# STLink_V3E_PWR.net
KiCad netlist of a schematic drawn in Altium Designer
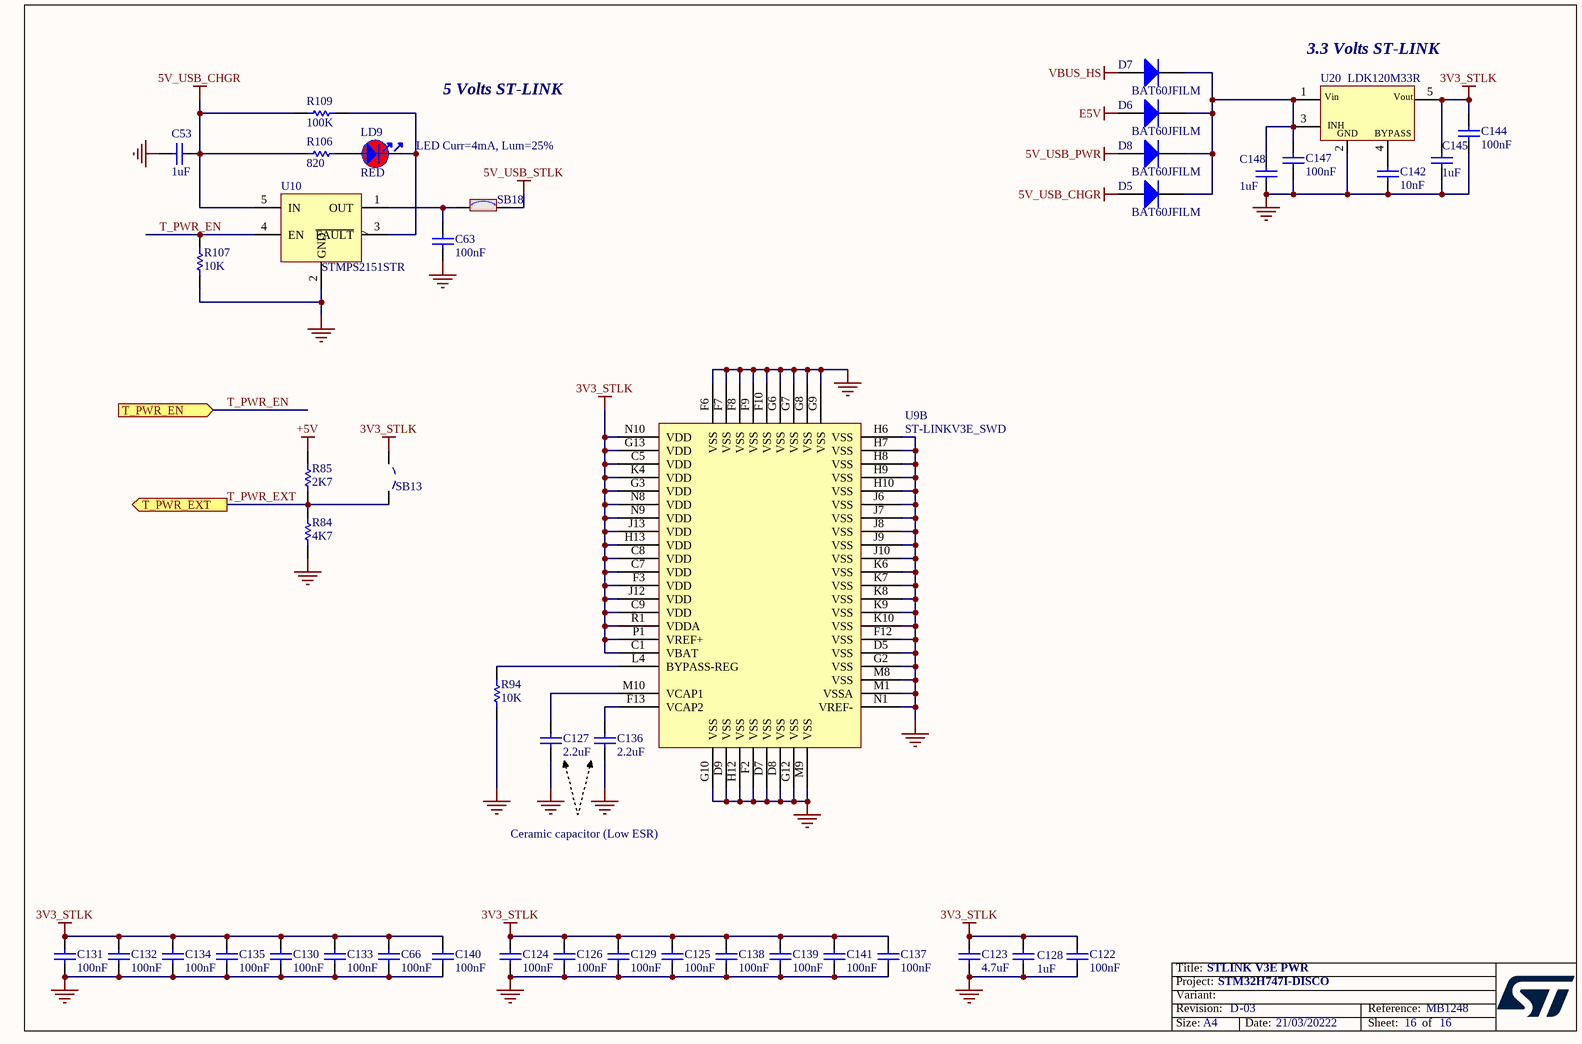
[diagram p0: STLink_V3E_PWR.SchDoc]

(export (version "E")
  (design (tool "Eeschema 10.0.6"))
  (components
    (comp (ref "C53")
      (value "1uF")
      (footprint "0603C")
      (description "Capacitor,1uF,16V,X5R,10%,0603")
      (fields
        (field (name "INTERNAL_PART_NUMBER") "MCD-00010")
        (field (name "MANUFACTURER_PART_NUMBER") "CC0603KRX5R7BB105")
        (field (name "PROVIDED_BY") "Subcon")
      )
      (libsource (lib "MCD_PARTS_database") (part "Capacitor"))
    )
    (comp (ref "C63")
      (value "100nF")
      (footprint "0603C")
      (description "Capacitor, MLCC, 100nF, 16V, X7R, 10%, 0402, T=0.5mm")
      (fields
        (field (name "INTERNAL_PART_NUMBER") "MCD-00006")
        (field (name "MANUFACTURER_PART_NUMBER") "CC0402KRX7R7BB104")
        (field (name "PROVIDED_BY") "Subcon")
      )
      (libsource (lib "MCD_PARTS_database") (part "Capacitor"))
    )
    (comp (ref "C66")
      (value "100nF")
      (footprint "0402C")
      (description "Capacitor,100nF,16V,X7R,10%,0402")
      (fields
        (field (name "INTERNAL_PART_NUMBER") "MCD-00102")
        (field (name "MANUFACTURER_PART_NUMBER") "CC0402KRX7R7BB104")
        (field (name "PROVIDED_BY") "Subcon")
      )
      (libsource (lib "MCD_PARTS_database") (part "Capacitor"))
    )
    (comp (ref "C122")
      (value "100nF")
      (footprint "0603C")
      (description "Capacitor,100nF,16V,X7R,10%,0603")
      (fields
        (field (name "INTERNAL_PART_NUMBER") "MCD-00211")
        (field (name "MANUFACTURER_PART_NUMBER") "CC0603KRX7R7BB104")
        (field (name "PROVIDED_BY") "Subcon")
      )
      (libsource (lib "MCD_PARTS_database") (part "Capacitor"))
    )
    (comp (ref "C123")
      (value "4.7uF")
      (footprint "0603C")
      (description "Capacitor,4.7uF,16V, X5R,10%,0603")
      (fields
        (field (name "INTERNAL_PART_NUMBER") "MCD-00009")
        (field (name "MANUFACTURER_PART_NUMBER") "CC0603KRX5R7BB475")
        (field (name "PROVIDED_BY") "subcon")
      )
      (libsource (lib "MCD_PARTS_database") (part "Capacitor"))
    )
    (comp (ref "C124")
      (value "100nF")
      (footprint "0402C")
      (description "Capacitor,100nF,16V,X7R,10%,0402")
      (fields
        (field (name "INTERNAL_PART_NUMBER") "MCD-00102")
        (field (name "MANUFACTURER_PART_NUMBER") "CC0402KRX7R7BB104")
        (field (name "PROVIDED_BY") "Subcon")
      )
      (libsource (lib "MCD_PARTS_database") (part "Capacitor"))
    )
    (comp (ref "C125")
      (value "100nF")
      (footprint "0402C")
      (description "Capacitor,100nF,16V,X7R,10%,0402")
      (fields
        (field (name "INTERNAL_PART_NUMBER") "MCD-00102")
        (field (name "MANUFACTURER_PART_NUMBER") "CC0402KRX7R7BB104")
        (field (name "PROVIDED_BY") "Subcon")
      )
      (libsource (lib "MCD_PARTS_database") (part "Capacitor"))
    )
    (comp (ref "C126")
      (value "100nF")
      (footprint "0402C")
      (description "Capacitor,100nF,16V,X7R,10%,0402")
      (fields
        (field (name "INTERNAL_PART_NUMBER") "MCD-00102")
        (field (name "MANUFACTURER_PART_NUMBER") "CC0402KRX7R7BB104")
        (field (name "PROVIDED_BY") "Subcon")
      )
      (libsource (lib "MCD_PARTS_database") (part "Capacitor"))
    )
    (comp (ref "C127")
      (value "2.2uF")
      (footprint "1206C")
      (description "Capacitor,2.2uF,16V, X7R,10%,1206")
      (fields
        (field (name "INTERNAL_PART_NUMBER") "MCD-00008")
        (field (name "MANUFACTURER_PART_NUMBER") "CC1206KKX7R7BB225")
        (field (name "PROVIDED_BY") "Subcon")
      )
      (libsource (lib "MCD_PARTS_database") (part "Capacitor"))
    )
    (comp (ref "C128")
      (value "1uF")
      (footprint "0603C")
      (description "Capacitor,1uF,16V,X5R,10%,0603")
      (fields
        (field (name "INTERNAL_PART_NUMBER") "MCD-00010")
        (field (name "MANUFACTURER_PART_NUMBER") "CC0603KRX5R7BB105")
        (field (name "PROVIDED_BY") "Subcon")
      )
      (libsource (lib "MCD_PARTS_database") (part "Capacitor"))
    )
    (comp (ref "C129")
      (value "100nF")
      (footprint "0402C")
      (description "Capacitor,100nF,16V,X7R,10%,0402")
      (fields
        (field (name "INTERNAL_PART_NUMBER") "MCD-00102")
        (field (name "MANUFACTURER_PART_NUMBER") "CC0402KRX7R7BB104")
        (field (name "PROVIDED_BY") "Subcon")
      )
      (libsource (lib "MCD_PARTS_database") (part "Capacitor"))
    )
    (comp (ref "C130")
      (value "100nF")
      (footprint "0402C")
      (description "Capacitor,100nF,16V,X7R,10%,0402")
      (fields
        (field (name "INTERNAL_PART_NUMBER") "MCD-00102")
        (field (name "MANUFACTURER_PART_NUMBER") "CC0402KRX7R7BB104")
        (field (name "PROVIDED_BY") "Subcon")
      )
      (libsource (lib "MCD_PARTS_database") (part "Capacitor"))
    )
    (comp (ref "C131")
      (value "100nF")
      (footprint "0402C")
      (description "Capacitor,100nF,16V,X7R,10%,0402")
      (fields
        (field (name "INTERNAL_PART_NUMBER") "MCD-00102")
        (field (name "MANUFACTURER_PART_NUMBER") "CC0402KRX7R7BB104")
        (field (name "PROVIDED_BY") "Subcon")
      )
      (libsource (lib "MCD_PARTS_database") (part "Capacitor"))
    )
    (comp (ref "C132")
      (value "100nF")
      (footprint "0402C")
      (description "Capacitor,100nF,16V,X7R,10%,0402")
      (fields
        (field (name "INTERNAL_PART_NUMBER") "MCD-00102")
        (field (name "MANUFACTURER_PART_NUMBER") "CC0402KRX7R7BB104")
        (field (name "PROVIDED_BY") "Subcon")
      )
      (libsource (lib "MCD_PARTS_database") (part "Capacitor"))
    )
    (comp (ref "C133")
      (value "100nF")
      (footprint "0402C")
      (description "Capacitor,100nF,16V,X7R,10%,0402")
      (fields
        (field (name "INTERNAL_PART_NUMBER") "MCD-00102")
        (field (name "MANUFACTURER_PART_NUMBER") "CC0402KRX7R7BB104")
        (field (name "PROVIDED_BY") "Subcon")
      )
      (libsource (lib "MCD_PARTS_database") (part "Capacitor"))
    )
    (comp (ref "C134")
      (value "100nF")
      (footprint "0402C")
      (description "Capacitor,100nF,16V,X7R,10%,0402")
      (fields
        (field (name "INTERNAL_PART_NUMBER") "MCD-00102")
        (field (name "MANUFACTURER_PART_NUMBER") "CC0402KRX7R7BB104")
        (field (name "PROVIDED_BY") "Subcon")
      )
      (libsource (lib "MCD_PARTS_database") (part "Capacitor"))
    )
    (comp (ref "C135")
      (value "100nF")
      (footprint "0402C")
      (description "Capacitor,100nF,16V,X7R,10%,0402")
      (fields
        (field (name "INTERNAL_PART_NUMBER") "MCD-00102")
        (field (name "MANUFACTURER_PART_NUMBER") "CC0402KRX7R7BB104")
        (field (name "PROVIDED_BY") "Subcon")
      )
      (libsource (lib "MCD_PARTS_database") (part "Capacitor"))
    )
    (comp (ref "C136")
      (value "2.2uF")
      (footprint "1206C")
      (description "Capacitor,2.2uF,16V, X7R,10%,1206")
      (fields
        (field (name "INTERNAL_PART_NUMBER") "MCD-00008")
        (field (name "MANUFACTURER_PART_NUMBER") "CC1206KKX7R7BB225")
        (field (name "PROVIDED_BY") "Subcon")
      )
      (libsource (lib "MCD_PARTS_database") (part "Capacitor"))
    )
    (comp (ref "C137")
      (value "100nF")
      (footprint "0402C")
      (description "Capacitor,100nF,16V,X7R,10%,0402")
      (fields
        (field (name "INTERNAL_PART_NUMBER") "MCD-00102")
        (field (name "MANUFACTURER_PART_NUMBER") "CC0402KRX7R7BB104")
        (field (name "PROVIDED_BY") "Subcon")
      )
      (libsource (lib "MCD_PARTS_database") (part "Capacitor"))
    )
    (comp (ref "C138")
      (value "100nF")
      (footprint "0402C")
      (description "Capacitor,100nF,16V,X7R,10%,0402")
      (fields
        (field (name "INTERNAL_PART_NUMBER") "MCD-00102")
        (field (name "MANUFACTURER_PART_NUMBER") "CC0402KRX7R7BB104")
        (field (name "PROVIDED_BY") "Subcon")
      )
      (libsource (lib "MCD_PARTS_database") (part "Capacitor"))
    )
    (comp (ref "C139")
      (value "100nF")
      (footprint "0402C")
      (description "Capacitor,100nF,16V,X7R,10%,0402")
      (fields
        (field (name "INTERNAL_PART_NUMBER") "MCD-00102")
        (field (name "MANUFACTURER_PART_NUMBER") "CC0402KRX7R7BB104")
        (field (name "PROVIDED_BY") "Subcon")
      )
      (libsource (lib "MCD_PARTS_database") (part "Capacitor"))
    )
    (comp (ref "C140")
      (value "100nF")
      (footprint "0402C")
      (description "Capacitor,100nF,16V,X7R,10%,0402")
      (fields
        (field (name "INTERNAL_PART_NUMBER") "MCD-00102")
        (field (name "MANUFACTURER_PART_NUMBER") "CC0402KRX7R7BB104")
        (field (name "PROVIDED_BY") "Subcon")
      )
      (libsource (lib "MCD_PARTS_database") (part "Capacitor"))
    )
    (comp (ref "C141")
      (value "100nF")
      (footprint "0402C")
      (description "Capacitor,100nF,16V,X7R,10%,0402")
      (fields
        (field (name "INTERNAL_PART_NUMBER") "MCD-00102")
        (field (name "MANUFACTURER_PART_NUMBER") "CC0402KRX7R7BB104")
        (field (name "PROVIDED_BY") "Subcon")
      )
      (libsource (lib "MCD_PARTS_database") (part "Capacitor"))
    )
    (comp (ref "C142")
      (value "10nF")
      (footprint "0603C")
      (description "Capacitor,10nF,50V,X7R,10%,0603")
      (fields
        (field (name "INTERNAL_PART_NUMBER") "MCD-00017")
        (field (name "MANUFACTURER_PART_NUMBER") "CC0603KRX7R9BB103")
        (field (name "PROVIDED_BY") "Subcon")
      )
      (libsource (lib "MCD_PARTS_database") (part "Capacitor"))
    )
    (comp (ref "C144")
      (value "100nF")
      (footprint "0603C")
      (description "Capacitor,100nF,16V,X7R,10%,0603")
      (fields
        (field (name "INTERNAL_PART_NUMBER") "MCD-00211")
        (field (name "MANUFACTURER_PART_NUMBER") "CC0603KRX7R7BB104")
        (field (name "PROVIDED_BY") "Subcon")
      )
      (libsource (lib "MCD_PARTS_database") (part "Capacitor"))
    )
    (comp (ref "C145")
      (value "1uF")
      (footprint "0603C")
      (description "Capacitor,1uF,16V,X5R,10%,0603")
      (fields
        (field (name "INTERNAL_PART_NUMBER") "MCD-00010")
        (field (name "MANUFACTURER_PART_NUMBER") "CC0603KRX5R7BB105")
        (field (name "PROVIDED_BY") "Subcon")
      )
      (libsource (lib "MCD_PARTS_database") (part "Capacitor"))
    )
    (comp (ref "C147")
      (value "100nF")
      (footprint "0603C")
      (description "Capacitor,100nF,16V,X7R,10%,0603")
      (fields
        (field (name "INTERNAL_PART_NUMBER") "MCD-00211")
        (field (name "MANUFACTURER_PART_NUMBER") "CC0603KRX7R7BB104")
        (field (name "PROVIDED_BY") "Subcon")
      )
      (libsource (lib "MCD_PARTS_database") (part "Capacitor"))
    )
    (comp (ref "C148")
      (value "1uF")
      (footprint "0603C")
      (description "Capacitor,1uF,6V3,X5R,10%,0603")
      (fields
        (field (name "INTERNAL_PART_NUMBER") "MCD-00238")
        (field (name "MANUFACTURER_PART_NUMBER") "CC0603KRX5R5BB105")
        (field (name "PROVIDED_BY") "Subcon")
      )
      (libsource (lib "MCD_PARTS_database") (part "Capacitor"))
    )
    (comp (ref "D5")
      (value "BAT60JFILM")
      (footprint "SOD-323")
      (fields (field (name "INTERNAL_PART_NUMBER") "MCD-00034"))
      (libsource (lib "MCD_PARTS_database") (part "BAT60JFILM"))
    )
    (comp (ref "D6")
      (value "BAT60JFILM")
      (footprint "SOD-323")
      (fields (field (name "INTERNAL_PART_NUMBER") "MCD-00034"))
      (libsource (lib "MCD_PARTS_database") (part "BAT60JFILM"))
    )
    (comp (ref "D7")
      (value "BAT60JFILM")
      (footprint "SOD-323")
      (fields (field (name "INTERNAL_PART_NUMBER") "MCD-00034"))
      (libsource (lib "MCD_PARTS_database") (part "BAT60JFILM"))
    )
    (comp (ref "D8")
      (value "BAT60JFILM")
      (footprint "SOD-323")
      (fields (field (name "INTERNAL_PART_NUMBER") "MCD-00034"))
      (libsource (lib "MCD_PARTS_database") (part "BAT60JFILM"))
    )
    (comp (ref "LD9")
      (value "RED")
      (footprint "0603D")
      (description "LED Red, 0603 SMD, 2V Forward Voltage")
      (fields
        (field (name "INTERNAL_PART_NUMBER") "MCD-00587")
        (field (name "MANUFACTURER_PART_NUMBER") "VLMS1300-GS08")
        (field (name "PROVIDED_BY") "Subcon")
      )
      (libsource (lib "MCD_PARTS_database") (part "LED_red"))
    )
    (comp (ref "R84")
      (value "4K7")
      (footprint "0402R")
      (description "Resistor,4K7,0402,1%,1/16W")
      (fields
        (field (name "INTERNAL_PART_NUMBER") "MCD-00065")
        (field (name "MANUFACTURER_PART_NUMBER") "RC0402FR-074K7L")
        (field (name "PROVIDED_BY") "Subcon")
      )
      (libsource (lib "MCD_PARTS_database") (part "Resistor"))
    )
    (comp (ref "R85")
      (value "2K7")
      (footprint "0402R")
      (description "Resistor,2K7,0402,1%,1/16W")
      (fields
        (field (name "INTERNAL_PART_NUMBER") "MCD-00055")
        (field (name "MANUFACTURER_PART_NUMBER") "RC0402FR-072K7L")
        (field (name "PROVIDED_BY") "Subcon")
      )
      (libsource (lib "MCD_PARTS_database") (part "Resistor"))
    )
    (comp (ref "R94")
      (value "10K")
      (footprint "0402R")
      (description "Resistor,10K,0402,1%,1/16W")
      (fields
        (field (name "INTERNAL_PART_NUMBER") "MCD-00053")
        (field (name "MANUFACTURER_PART_NUMBER") "RC0402FR-0710KL")
        (field (name "PROVIDED_BY") "subcon")
      )
      (libsource (lib "MCD_PARTS_database") (part "Resistor"))
    )
    (comp (ref "R106")
      (value "820")
      (footprint "0603R")
      (description "Resistor,820R,0402,1%,1/16W")
      (fields
        (field (name "INTERNAL_PART_NUMBER") "MCD-00527")
        (field (name "MANUFACTURER_PART_NUMBER") "RC0402FR-07820RL")
        (field (name "PROVIDED_BY") "Subcon")
      )
      (libsource (lib "MCD_PARTS_database") (part "Resistor"))
    )
    (comp (ref "R107")
      (value "10K")
      (footprint "0603R")
      (description "Resistor,10K,0402,1%,1/16W")
      (fields
        (field (name "INTERNAL_PART_NUMBER") "MCD-00053")
        (field (name "MANUFACTURER_PART_NUMBER") "RC0402FR-0710KL")
        (field (name "PROVIDED_BY") "subcon")
      )
      (libsource (lib "MCD_PARTS_database") (part "Resistor"))
    )
    (comp (ref "R109")
      (value "100K")
      (footprint "0402R")
      (description "Resistor,100K,0402,1%,1/16W")
      (fields
        (field (name "INTERNAL_PART_NUMBER") "MCD-00059")
        (field (name "MANUFACTURER_PART_NUMBER") "RC0402FR-07100KL")
        (field (name "PROVIDED_BY") "Subcon")
      )
      (libsource (lib "MCD_PARTS_database") (part "Resistor"))
    )
    (comp (ref "SB13")
      (value "Solder Bridge OFF")
      (footprint "SB_0603")
      (libsource (lib "MCD_TOOLS") (part "SB_OFF"))
    )
    (comp (ref "SB18")
      (value "Solder Bridge ON")
      (footprint "SB_0603")
      (libsource (lib "MCD_TOOLS") (part "SB_ON"))
    )
    (comp (ref "U9")
      (value "ST-LINKV3E_SWD")
      (footprint "BGA176_0R65_10x10")
      (description "STM32F723IEK  (STM32F7 LittleBirdie) BGA176")
      (fields (field (name "INTERNAL_PART_NUMBER") "MCD-00596"))
      (libsource (lib "MB1248_1") (part "ST-LINKV3E_SWD"))
    )
    (comp (ref "U10")
      (value "STMPS2151STR")
      (footprint "SOT23-5")
      (description "500mA, Enhanced single channel power switches with active high enable pin")
      (fields
        (field (name "INTERNAL_PART_NUMBER") "MCD-00159")
        (field (name "MANUFACTURER") "STMICROELECTRONICS")
        (field (name "PROVIDED_BY") "Subcon")
      )
      (libsource (lib "MCD_PARTS_database") (part "STMPS2151STR"))
    )
    (comp (ref "U20")
      (value "LDK120M33R")
      (footprint "SOT23-5")
      (description "Ultra low drop-low noise BiCMOS voltage, regulators low ESR capacitors compatible")
      (fields (field (name "INTERNAL_PART_NUMBER") "MCD-00086"))
      (libsource (lib "MCD_PARTS_database") (part "LD3985M33R"))
    )
  )
  (nets
    (net (code "1") (name "+5V") (class "Default")
      (node (ref "R85") (pin "2") (pinfunction "2_2") (pintype "passive"))
    )
    (net (code "2") (name "/T_PWR_EN") (class "Default")
      (node (ref "R107") (pin "2") (pinfunction "2_2") (pintype "passive"))
      (node (ref "U10") (pin "4") (pinfunction "EN_4") (pintype "passive"))
    )
    (net (code "3") (name "/T_PWR_EXT") (class "Default")
      (node (ref "R84") (pin "2") (pinfunction "2_2") (pintype "passive"))
      (node (ref "R85") (pin "1") (pinfunction "1_1") (pintype "passive"))
      (node (ref "SB13") (pin "2") (pinfunction "2_2") (pintype "passive"))
    )
    (net (code "4") (name "3V3_STLK") (class "Default")
      (node (ref "C122") (pin "2") (pinfunction "2_2") (pintype "passive"))
      (node (ref "C123") (pin "2") (pinfunction "2_2") (pintype "passive"))
      (node (ref "C124") (pin "2") (pinfunction "2_2") (pintype "passive"))
      (node (ref "C125") (pin "2") (pinfunction "2_2") (pintype "passive"))
      (node (ref "C126") (pin "2") (pinfunction "2_2") (pintype "passive"))
      (node (ref "C128") (pin "2") (pinfunction "2_2") (pintype "passive"))
      (node (ref "C129") (pin "2") (pinfunction "2_2") (pintype "passive"))
      (node (ref "C130") (pin "2") (pinfunction "2_2") (pintype "passive"))
      (node (ref "C131") (pin "2") (pinfunction "2_2") (pintype "passive"))
      (node (ref "C132") (pin "2") (pinfunction "2_2") (pintype "passive"))
      (node (ref "C133") (pin "2") (pinfunction "2_2") (pintype "passive"))
      (node (ref "C134") (pin "2") (pinfunction "2_2") (pintype "passive"))
      (node (ref "C135") (pin "2") (pinfunction "2_2") (pintype "passive"))
      (node (ref "C137") (pin "2") (pinfunction "2_2") (pintype "passive"))
      (node (ref "C138") (pin "2") (pinfunction "2_2") (pintype "passive"))
      (node (ref "C139") (pin "2") (pinfunction "2_2") (pintype "passive"))
      (node (ref "C140") (pin "2") (pinfunction "2_2") (pintype "passive"))
      (node (ref "C141") (pin "2") (pinfunction "2_2") (pintype "passive"))
      (node (ref "C144") (pin "2") (pinfunction "2_2") (pintype "passive"))
      (node (ref "C145") (pin "2") (pinfunction "2_2") (pintype "passive"))
      (node (ref "C66") (pin "2") (pinfunction "2_2") (pintype "passive"))
      (node (ref "SB13") (pin "1") (pinfunction "1_1") (pintype "passive"))
      (node (ref "U20") (pin "5") (pinfunction "Vout_5") (pintype "passive"))
      (node (ref "U9") (pin "C1") (pinfunction "VBAT_C1") (pintype "passive"))
      (node (ref "U9") (pin "C5") (pinfunction "VDD_C5") (pintype "passive"))
      (node (ref "U9") (pin "C7") (pinfunction "VDD_C7") (pintype "passive"))
      (node (ref "U9") (pin "C8") (pinfunction "VDD_C8") (pintype "passive"))
      (node (ref "U9") (pin "C9") (pinfunction "VDD_C9") (pintype "passive"))
      (node (ref "U9") (pin "F3") (pinfunction "VDD_F3") (pintype "passive"))
      (node (ref "U9") (pin "G13") (pinfunction "VDD_G13") (pintype "passive"))
      (node (ref "U9") (pin "G3") (pinfunction "VDD_G3") (pintype "passive"))
      (node (ref "U9") (pin "H13") (pinfunction "VDD_H13") (pintype "passive"))
      (node (ref "U9") (pin "J12") (pinfunction "VDD_J12") (pintype "passive"))
      (node (ref "U9") (pin "J13") (pinfunction "VDD_J13") (pintype "passive"))
      (node (ref "U9") (pin "K4") (pinfunction "VDD_K4") (pintype "passive"))
      (node (ref "U9") (pin "N10") (pinfunction "VDD_N10") (pintype "passive"))
      (node (ref "U9") (pin "N8") (pinfunction "VDD_N8") (pintype "passive"))
      (node (ref "U9") (pin "N9") (pinfunction "VDD_N9") (pintype "passive"))
      (node (ref "U9") (pin "P1") (pinfunction "VREF+_P1") (pintype "passive"))
      (node (ref "U9") (pin "R1") (pinfunction "VDDA_R1") (pintype "passive"))
    )
    (net (code "5") (name "5V_USB_CHGR") (class "Default")
      (node (ref "C53") (pin "1") (pinfunction "1_1") (pintype "passive"))
      (node (ref "D5") (pin "1") (pinfunction "A_1") (pintype "passive"))
      (node (ref "R106") (pin "1") (pinfunction "1_1") (pintype "passive"))
      (node (ref "R109") (pin "2") (pinfunction "2_2") (pintype "passive"))
      (node (ref "U10") (pin "5") (pinfunction "IN_5") (pintype "passive"))
    )
    (net (code "6") (name "5V_USB_PWR") (class "Default")
      (node (ref "D8") (pin "1") (pinfunction "A_1") (pintype "passive"))
    )
    (net (code "7") (name "5V_USB_STLK") (class "Default")
      (node (ref "SB18") (pin "2") (pinfunction "2_2") (pintype "passive"))
    )
    (net (code "8") (name "E5V") (class "Default")
      (node (ref "D6") (pin "1") (pinfunction "A_1") (pintype "passive"))
    )
    (net (code "9") (name "GND") (class "Default")
      (node (ref "C122") (pin "1") (pinfunction "1_1") (pintype "passive"))
      (node (ref "C123") (pin "1") (pinfunction "1_1") (pintype "passive"))
      (node (ref "C124") (pin "1") (pinfunction "1_1") (pintype "passive"))
      (node (ref "C125") (pin "1") (pinfunction "1_1") (pintype "passive"))
      (node (ref "C126") (pin "1") (pinfunction "1_1") (pintype "passive"))
      (node (ref "C127") (pin "1") (pinfunction "1_1") (pintype "passive"))
      (node (ref "C128") (pin "1") (pinfunction "1_1") (pintype "passive"))
      (node (ref "C129") (pin "1") (pinfunction "1_1") (pintype "passive"))
      (node (ref "C130") (pin "1") (pinfunction "1_1") (pintype "passive"))
      (node (ref "C131") (pin "1") (pinfunction "1_1") (pintype "passive"))
      (node (ref "C132") (pin "1") (pinfunction "1_1") (pintype "passive"))
      (node (ref "C133") (pin "1") (pinfunction "1_1") (pintype "passive"))
      (node (ref "C134") (pin "1") (pinfunction "1_1") (pintype "passive"))
      (node (ref "C135") (pin "1") (pinfunction "1_1") (pintype "passive"))
      (node (ref "C136") (pin "1") (pinfunction "1_1") (pintype "passive"))
      (node (ref "C137") (pin "1") (pinfunction "1_1") (pintype "passive"))
      (node (ref "C138") (pin "1") (pinfunction "1_1") (pintype "passive"))
      (node (ref "C139") (pin "1") (pinfunction "1_1") (pintype "passive"))
      (node (ref "C140") (pin "1") (pinfunction "1_1") (pintype "passive"))
      (node (ref "C141") (pin "1") (pinfunction "1_1") (pintype "passive"))
      (node (ref "C142") (pin "1") (pinfunction "1_1") (pintype "passive"))
      (node (ref "C144") (pin "1") (pinfunction "1_1") (pintype "passive"))
      (node (ref "C145") (pin "1") (pinfunction "1_1") (pintype "passive"))
      (node (ref "C147") (pin "1") (pinfunction "1_1") (pintype "passive"))
      (node (ref "C148") (pin "2") (pinfunction "2_2") (pintype "passive"))
      (node (ref "C53") (pin "2") (pinfunction "2_2") (pintype "passive"))
      (node (ref "C63") (pin "1") (pinfunction "1_1") (pintype "passive"))
      (node (ref "C66") (pin "1") (pinfunction "1_1") (pintype "passive"))
      (node (ref "R107") (pin "1") (pinfunction "1_1") (pintype "passive"))
      (node (ref "R84") (pin "1") (pinfunction "1_1") (pintype "passive"))
      (node (ref "R94") (pin "1") (pinfunction "1_1") (pintype "passive"))
      (node (ref "U10") (pin "2") (pinfunction "GND_2") (pintype "passive"))
      (node (ref "U20") (pin "2") (pinfunction "GND_2") (pintype "passive"))
      (node (ref "U9") (pin "D5") (pinfunction "VSS_D5") (pintype "passive"))
      (node (ref "U9") (pin "D7") (pinfunction "VSS_D7") (pintype "passive"))
      (node (ref "U9") (pin "D8") (pinfunction "VSS_D8") (pintype "passive"))
      (node (ref "U9") (pin "D9") (pinfunction "VSS_D9") (pintype "passive"))
      (node (ref "U9") (pin "F10") (pinfunction "VSS_F10") (pintype "passive"))
      (node (ref "U9") (pin "F12") (pinfunction "VSS_F12") (pintype "passive"))
      (node (ref "U9") (pin "F2") (pinfunction "VSS_F2") (pintype "passive"))
      (node (ref "U9") (pin "F6") (pinfunction "VSS_F6") (pintype "passive"))
      (node (ref "U9") (pin "F7") (pinfunction "VSS_F7") (pintype "passive"))
      (node (ref "U9") (pin "F8") (pinfunction "VSS_F8") (pintype "passive"))
      (node (ref "U9") (pin "F9") (pinfunction "VSS_F9") (pintype "passive"))
      (node (ref "U9") (pin "G10") (pinfunction "VSS_G10") (pintype "passive"))
      (node (ref "U9") (pin "G12") (pinfunction "VSS_G12") (pintype "passive"))
      (node (ref "U9") (pin "G2") (pinfunction "VSS_G2") (pintype "passive"))
      (node (ref "U9") (pin "G6") (pinfunction "VSS_G6") (pintype "passive"))
      (node (ref "U9") (pin "G7") (pinfunction "VSS_G7") (pintype "passive"))
      (node (ref "U9") (pin "G8") (pinfunction "VSS_G8") (pintype "passive"))
      (node (ref "U9") (pin "G9") (pinfunction "VSS_G9") (pintype "passive"))
      (node (ref "U9") (pin "H10") (pinfunction "VSS_H10") (pintype "passive"))
      (node (ref "U9") (pin "H12") (pinfunction "VSS_H12") (pintype "passive"))
      (node (ref "U9") (pin "H6") (pinfunction "VSS_H6") (pintype "passive"))
      (node (ref "U9") (pin "H7") (pinfunction "VSS_H7") (pintype "passive"))
      (node (ref "U9") (pin "H8") (pinfunction "VSS_H8") (pintype "passive"))
      (node (ref "U9") (pin "H9") (pinfunction "VSS_H9") (pintype "passive"))
      (node (ref "U9") (pin "J10") (pinfunction "VSS_J10") (pintype "passive"))
      (node (ref "U9") (pin "J6") (pinfunction "VSS_J6") (pintype "passive"))
      (node (ref "U9") (pin "J7") (pinfunction "VSS_J7") (pintype "passive"))
      (node (ref "U9") (pin "J8") (pinfunction "VSS_J8") (pintype "passive"))
      (node (ref "U9") (pin "J9") (pinfunction "VSS_J9") (pintype "passive"))
      (node (ref "U9") (pin "K10") (pinfunction "VSS_K10") (pintype "passive"))
      (node (ref "U9") (pin "K6") (pinfunction "VSS_K6") (pintype "passive"))
      (node (ref "U9") (pin "K7") (pinfunction "VSS_K7") (pintype "passive"))
      (node (ref "U9") (pin "K8") (pinfunction "VSS_K8") (pintype "passive"))
      (node (ref "U9") (pin "K9") (pinfunction "VSS_K9") (pintype "passive"))
      (node (ref "U9") (pin "M1") (pinfunction "VSSA_M1") (pintype "passive"))
      (node (ref "U9") (pin "M8") (pinfunction "VSS_M8") (pintype "passive"))
      (node (ref "U9") (pin "M9") (pinfunction "VSS_M9") (pintype "passive"))
      (node (ref "U9") (pin "N1") (pinfunction "VREF-_N1") (pintype "passive"))
    )
    (net (code "10") (name "Net-(D5-K)") (class "Default")
      (node (ref "C147") (pin "2") (pinfunction "2_2") (pintype "passive"))
      (node (ref "C148") (pin "1") (pinfunction "1_1") (pintype "passive"))
      (node (ref "D5") (pin "2") (pinfunction "K_2") (pintype "passive"))
      (node (ref "D6") (pin "2") (pinfunction "K_2") (pintype "passive"))
      (node (ref "D7") (pin "2") (pinfunction "K_2") (pintype "passive"))
      (node (ref "D8") (pin "2") (pinfunction "K_2") (pintype "passive"))
      (node (ref "U20") (pin "1") (pinfunction "Vin_1") (pintype "passive"))
      (node (ref "U20") (pin "3") (pinfunction "CE_3") (pintype "passive"))
    )
    (net (code "11") (name "Net-(LD9-Pad1)") (class "Default")
      (node (ref "LD9") (pin "1") (pintype "passive"))
      (node (ref "R106") (pin "2") (pinfunction "2_2") (pintype "passive"))
    )
    (net (code "12") (name "Net-(U9B-BYPASS-REG)") (class "Default")
      (node (ref "R94") (pin "2") (pinfunction "2_2") (pintype "passive"))
      (node (ref "U9") (pin "L4") (pinfunction "BYPASS-REG_L4") (pintype "passive"))
    )
    (net (code "13") (name "Net-(U9B-VCAP1)") (class "Default")
      (node (ref "C127") (pin "2") (pinfunction "2_2") (pintype "passive"))
      (node (ref "U9") (pin "M10") (pinfunction "VCAP1_M10") (pintype "passive"))
    )
    (net (code "14") (name "Net-(U9B-VCAP2)") (class "Default")
      (node (ref "C136") (pin "2") (pinfunction "2_2") (pintype "passive"))
      (node (ref "U9") (pin "F13") (pinfunction "VCAP2_F13") (pintype "passive"))
    )
    (net (code "15") (name "Net-(U10-OUT)") (class "Default")
      (node (ref "C63") (pin "2") (pinfunction "2_2") (pintype "passive"))
      (node (ref "SB18") (pin "1") (pinfunction "1_1") (pintype "passive"))
      (node (ref "U10") (pin "1") (pinfunction "OUT_1") (pintype "passive"))
    )
    (net (code "16") (name "Net-(U10-~{FAULT})") (class "Default")
      (node (ref "LD9") (pin "2") (pintype "passive"))
      (node (ref "R109") (pin "1") (pinfunction "1_1") (pintype "passive"))
      (node (ref "U10") (pin "3") (pinfunction "~{FAULT}_3") (pintype "passive"))
    )
    (net (code "17") (name "Net-(U20-BYPASS)") (class "Default")
      (node (ref "C142") (pin "2") (pinfunction "2_2") (pintype "passive"))
      (node (ref "U20") (pin "4") (pinfunction "BYPASS_4") (pintype "passive"))
    )
    (net (code "18") (name "VBUS_HS") (class "Default")
      (node (ref "D7") (pin "1") (pinfunction "A_1") (pintype "passive"))
    )
  )
)
